# ShittyPanel.net
KiCad netlist of a schematic drawn in EAGLE
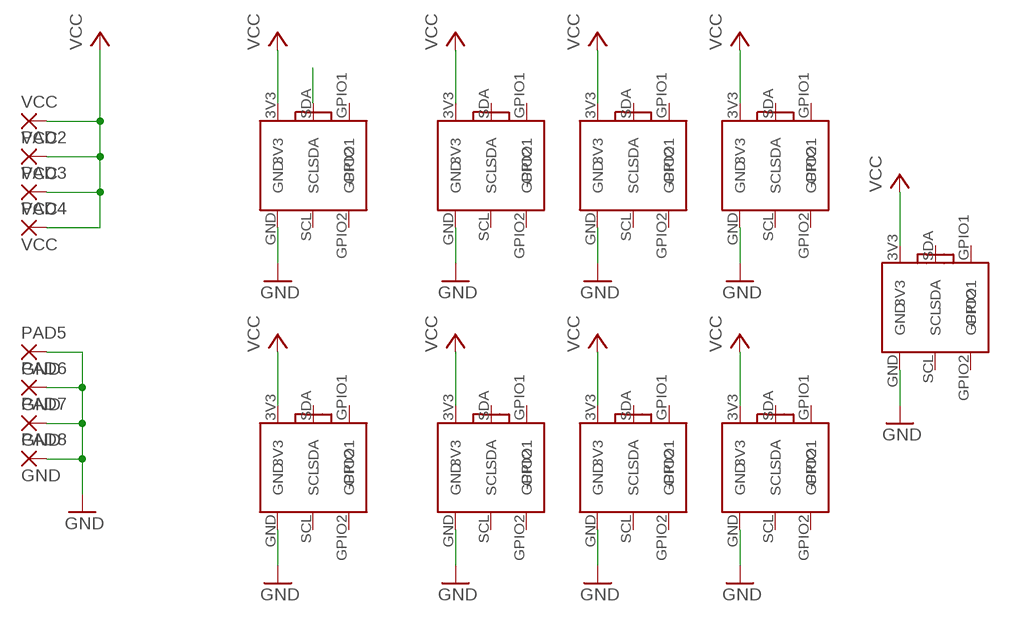
[diagram p0: schematic, sheet 1]

(export (version "E")
  (design (tool "Eeschema 10.0.6"))
  (components
    (comp (ref "PAD2")
      (value "VCC")
      (footprint "eagle-import:SMD2,54-5,08")
      (libsource (lib "eagle-import") (part "SMD5"))
    )
    (comp (ref "PAD3")
      (value "VCC")
      (footprint "eagle-import:SMD2,54-5,08")
      (libsource (lib "eagle-import") (part "SMD5"))
    )
    (comp (ref "PAD4")
      (value "VCC")
      (footprint "eagle-import:SMD2,54-5,08")
      (libsource (lib "eagle-import") (part "SMD5"))
    )
    (comp (ref "PAD5")
      (value "GND")
      (footprint "eagle-import:SMD2,54-5,08")
      (libsource (lib "eagle-import") (part "SMD5"))
    )
    (comp (ref "PAD6")
      (value "GND")
      (footprint "eagle-import:SMD2,54-5,08")
      (libsource (lib "eagle-import") (part "SMD5"))
    )
    (comp (ref "PAD7")
      (value "GND")
      (footprint "eagle-import:SMD2,54-5,08")
      (libsource (lib "eagle-import") (part "SMD5"))
    )
    (comp (ref "PAD8")
      (value "GND")
      (footprint "eagle-import:SMD2,54-5,08")
      (libsource (lib "eagle-import") (part "SMD5"))
    )
    (comp (ref "U$1")
      (value "SHITTYADDON2")
      (footprint "eagle-import:SHITTYADDON2")
      (libsource (lib "eagle-import") (part "SHITTYADDON2"))
    )
    (comp (ref "U$2")
      (value "SHITTYADDON2")
      (footprint "eagle-import:SHITTYADDON2")
      (libsource (lib "eagle-import") (part "SHITTYADDON2"))
    )
    (comp (ref "U$3")
      (value "SHITTYADDON2")
      (footprint "eagle-import:SHITTYADDON2")
      (libsource (lib "eagle-import") (part "SHITTYADDON2"))
    )
    (comp (ref "U$4")
      (value "SHITTYADDON2")
      (footprint "eagle-import:SHITTYADDON2")
      (libsource (lib "eagle-import") (part "SHITTYADDON2"))
    )
    (comp (ref "U$5")
      (value "SHITTYADDON2")
      (footprint "eagle-import:SHITTYADDON2")
      (libsource (lib "eagle-import") (part "SHITTYADDON2"))
    )
    (comp (ref "U$6")
      (value "SHITTYADDON2")
      (footprint "eagle-import:SHITTYADDON2")
      (libsource (lib "eagle-import") (part "SHITTYADDON2"))
    )
    (comp (ref "U$7")
      (value "SHITTYADDON2")
      (footprint "eagle-import:SHITTYADDON2")
      (libsource (lib "eagle-import") (part "SHITTYADDON2"))
    )
    (comp (ref "U$8")
      (value "SHITTYADDON2")
      (footprint "eagle-import:SHITTYADDON2")
      (libsource (lib "eagle-import") (part "SHITTYADDON2"))
    )
    (comp (ref "U$9")
      (value "SHITTYADDON2")
      (footprint "eagle-import:SHITTYADDON2")
      (libsource (lib "eagle-import") (part "SHITTYADDON2"))
    )
    (comp (ref "VCC")
      (value "VCC")
      (footprint "eagle-import:SMD2,54-5,08")
      (libsource (lib "eagle-import") (part "SMD5"))
    )
  )
  (nets
    (net (code "1") (name "GND") (class "Default")
      (node (ref "PAD5") (pin "1") (pinfunction "P_1") (pintype "passive"))
      (node (ref "PAD6") (pin "1") (pinfunction "P_1") (pintype "passive"))
      (node (ref "PAD7") (pin "1") (pinfunction "P_1") (pintype "passive"))
      (node (ref "PAD8") (pin "1") (pinfunction "P_1") (pintype "passive"))
      (node (ref "U$1") (pin "GND") (pinfunction "GND_GND") (pintype "bidirectional"))
      (node (ref "U$2") (pin "GND") (pinfunction "GND_GND") (pintype "bidirectional"))
      (node (ref "U$3") (pin "GND") (pinfunction "GND_GND") (pintype "bidirectional"))
      (node (ref "U$4") (pin "GND") (pinfunction "GND_GND") (pintype "bidirectional"))
      (node (ref "U$5") (pin "GND") (pinfunction "GND_GND") (pintype "bidirectional"))
      (node (ref "U$6") (pin "GND") (pinfunction "GND_GND") (pintype "bidirectional"))
      (node (ref "U$7") (pin "GND") (pinfunction "GND_GND") (pintype "bidirectional"))
      (node (ref "U$8") (pin "GND") (pinfunction "GND_GND") (pintype "bidirectional"))
      (node (ref "U$9") (pin "GND") (pinfunction "GND_GND") (pintype "bidirectional"))
    )
    (net (code "2") (name "VCC") (class "Default")
      (node (ref "PAD2") (pin "1") (pinfunction "P_1") (pintype "passive"))
      (node (ref "PAD3") (pin "1") (pinfunction "P_1") (pintype "passive"))
      (node (ref "PAD4") (pin "1") (pinfunction "P_1") (pintype "passive"))
      (node (ref "U$1") (pin "3V3") (pinfunction "3V3_3V3") (pintype "bidirectional"))
      (node (ref "U$2") (pin "3V3") (pinfunction "3V3_3V3") (pintype "bidirectional"))
      (node (ref "U$3") (pin "3V3") (pinfunction "3V3_3V3") (pintype "bidirectional"))
      (node (ref "U$4") (pin "3V3") (pinfunction "3V3_3V3") (pintype "bidirectional"))
      (node (ref "U$5") (pin "3V3") (pinfunction "3V3_3V3") (pintype "bidirectional"))
      (node (ref "U$6") (pin "3V3") (pinfunction "3V3_3V3") (pintype "bidirectional"))
      (node (ref "U$7") (pin "3V3") (pinfunction "3V3_3V3") (pintype "bidirectional"))
      (node (ref "U$8") (pin "3V3") (pinfunction "3V3_3V3") (pintype "bidirectional"))
      (node (ref "U$9") (pin "3V3") (pinfunction "3V3_3V3") (pintype "bidirectional"))
      (node (ref "VCC") (pin "1") (pinfunction "P_1") (pintype "passive"))
    )
    (net (code "3") (name "unconnected-(U$1-PadGPIO1)") (class "Default")
      (node (ref "U$1") (pin "GPIO1") (pinfunction "GPIO1_GPIO1") (pintype "bidirectional"))
    )
    (net (code "4") (name "unconnected-(U$1-PadGPIO2)") (class "Default")
      (node (ref "U$1") (pin "GPIO2") (pinfunction "GPIO2_GPIO2") (pintype "bidirectional"))
    )
    (net (code "5") (name "unconnected-(U$1-PadSCL)") (class "Default")
      (node (ref "U$1") (pin "SCL") (pinfunction "SCL_SCL") (pintype "bidirectional"))
    )
    (net (code "6") (name "unconnected-(U$1-PadSDA)") (class "Default")
      (node (ref "U$1") (pin "SDA") (pinfunction "SDA_SDA") (pintype "bidirectional"))
    )
    (net (code "7") (name "unconnected-(U$2-PadGPIO1)") (class "Default")
      (node (ref "U$2") (pin "GPIO1") (pinfunction "GPIO1_GPIO1") (pintype "bidirectional"))
    )
    (net (code "8") (name "unconnected-(U$2-PadGPIO2)") (class "Default")
      (node (ref "U$2") (pin "GPIO2") (pinfunction "GPIO2_GPIO2") (pintype "bidirectional"))
    )
    (net (code "9") (name "unconnected-(U$2-PadSCL)") (class "Default")
      (node (ref "U$2") (pin "SCL") (pinfunction "SCL_SCL") (pintype "bidirectional"))
    )
    (net (code "10") (name "unconnected-(U$2-PadSDA)") (class "Default")
      (node (ref "U$2") (pin "SDA") (pinfunction "SDA_SDA") (pintype "bidirectional"))
    )
    (net (code "11") (name "unconnected-(U$3-PadGPIO1)") (class "Default")
      (node (ref "U$3") (pin "GPIO1") (pinfunction "GPIO1_GPIO1") (pintype "bidirectional"))
    )
    (net (code "12") (name "unconnected-(U$3-PadGPIO2)") (class "Default")
      (node (ref "U$3") (pin "GPIO2") (pinfunction "GPIO2_GPIO2") (pintype "bidirectional"))
    )
    (net (code "13") (name "unconnected-(U$3-PadSCL)") (class "Default")
      (node (ref "U$3") (pin "SCL") (pinfunction "SCL_SCL") (pintype "bidirectional"))
    )
    (net (code "14") (name "unconnected-(U$3-PadSDA)") (class "Default")
      (node (ref "U$3") (pin "SDA") (pinfunction "SDA_SDA") (pintype "bidirectional"))
    )
    (net (code "15") (name "unconnected-(U$4-PadGPIO1)") (class "Default")
      (node (ref "U$4") (pin "GPIO1") (pinfunction "GPIO1_GPIO1") (pintype "bidirectional"))
    )
    (net (code "16") (name "unconnected-(U$4-PadGPIO2)") (class "Default")
      (node (ref "U$4") (pin "GPIO2") (pinfunction "GPIO2_GPIO2") (pintype "bidirectional"))
    )
    (net (code "17") (name "unconnected-(U$4-PadSCL)") (class "Default")
      (node (ref "U$4") (pin "SCL") (pinfunction "SCL_SCL") (pintype "bidirectional"))
    )
    (net (code "18") (name "unconnected-(U$4-PadSDA)") (class "Default")
      (node (ref "U$4") (pin "SDA") (pinfunction "SDA_SDA") (pintype "bidirectional"))
    )
    (net (code "19") (name "unconnected-(U$5-PadGPIO1)") (class "Default")
      (node (ref "U$5") (pin "GPIO1") (pinfunction "GPIO1_GPIO1") (pintype "bidirectional"))
    )
    (net (code "20") (name "unconnected-(U$5-PadGPIO2)") (class "Default")
      (node (ref "U$5") (pin "GPIO2") (pinfunction "GPIO2_GPIO2") (pintype "bidirectional"))
    )
    (net (code "21") (name "unconnected-(U$5-PadSCL)") (class "Default")
      (node (ref "U$5") (pin "SCL") (pinfunction "SCL_SCL") (pintype "bidirectional"))
    )
    (net (code "22") (name "unconnected-(U$5-PadSDA)") (class "Default")
      (node (ref "U$5") (pin "SDA") (pinfunction "SDA_SDA") (pintype "bidirectional"))
    )
    (net (code "23") (name "unconnected-(U$6-PadGPIO1)") (class "Default")
      (node (ref "U$6") (pin "GPIO1") (pinfunction "GPIO1_GPIO1") (pintype "bidirectional"))
    )
    (net (code "24") (name "unconnected-(U$6-PadGPIO2)") (class "Default")
      (node (ref "U$6") (pin "GPIO2") (pinfunction "GPIO2_GPIO2") (pintype "bidirectional"))
    )
    (net (code "25") (name "unconnected-(U$6-PadSCL)") (class "Default")
      (node (ref "U$6") (pin "SCL") (pinfunction "SCL_SCL") (pintype "bidirectional"))
    )
    (net (code "26") (name "unconnected-(U$6-PadSDA)") (class "Default")
      (node (ref "U$6") (pin "SDA") (pinfunction "SDA_SDA") (pintype "bidirectional"))
    )
    (net (code "27") (name "unconnected-(U$7-PadGPIO1)") (class "Default")
      (node (ref "U$7") (pin "GPIO1") (pinfunction "GPIO1_GPIO1") (pintype "bidirectional"))
    )
    (net (code "28") (name "unconnected-(U$7-PadGPIO2)") (class "Default")
      (node (ref "U$7") (pin "GPIO2") (pinfunction "GPIO2_GPIO2") (pintype "bidirectional"))
    )
    (net (code "29") (name "unconnected-(U$7-PadSCL)") (class "Default")
      (node (ref "U$7") (pin "SCL") (pinfunction "SCL_SCL") (pintype "bidirectional"))
    )
    (net (code "30") (name "unconnected-(U$7-PadSDA)") (class "Default")
      (node (ref "U$7") (pin "SDA") (pinfunction "SDA_SDA") (pintype "bidirectional"))
    )
    (net (code "31") (name "unconnected-(U$8-PadGPIO1)") (class "Default")
      (node (ref "U$8") (pin "GPIO1") (pinfunction "GPIO1_GPIO1") (pintype "bidirectional"))
    )
    (net (code "32") (name "unconnected-(U$8-PadGPIO2)") (class "Default")
      (node (ref "U$8") (pin "GPIO2") (pinfunction "GPIO2_GPIO2") (pintype "bidirectional"))
    )
    (net (code "33") (name "unconnected-(U$8-PadSCL)") (class "Default")
      (node (ref "U$8") (pin "SCL") (pinfunction "SCL_SCL") (pintype "bidirectional"))
    )
    (net (code "34") (name "unconnected-(U$8-PadSDA)") (class "Default")
      (node (ref "U$8") (pin "SDA") (pinfunction "SDA_SDA") (pintype "bidirectional"))
    )
    (net (code "35") (name "unconnected-(U$9-PadGPIO1)") (class "Default")
      (node (ref "U$9") (pin "GPIO1") (pinfunction "GPIO1_GPIO1") (pintype "bidirectional"))
    )
    (net (code "36") (name "unconnected-(U$9-PadGPIO2)") (class "Default")
      (node (ref "U$9") (pin "GPIO2") (pinfunction "GPIO2_GPIO2") (pintype "bidirectional"))
    )
    (net (code "37") (name "unconnected-(U$9-PadSCL)") (class "Default")
      (node (ref "U$9") (pin "SCL") (pinfunction "SCL_SCL") (pintype "bidirectional"))
    )
    (net (code "38") (name "unconnected-(U$9-PadSDA)") (class "Default")
      (node (ref "U$9") (pin "SDA") (pinfunction "SDA_SDA") (pintype "bidirectional"))
    )
  )
)
